# 1-Schematic_210_Project_Wearable.net
KiCad netlist of a schematic drawn in EasyEDA
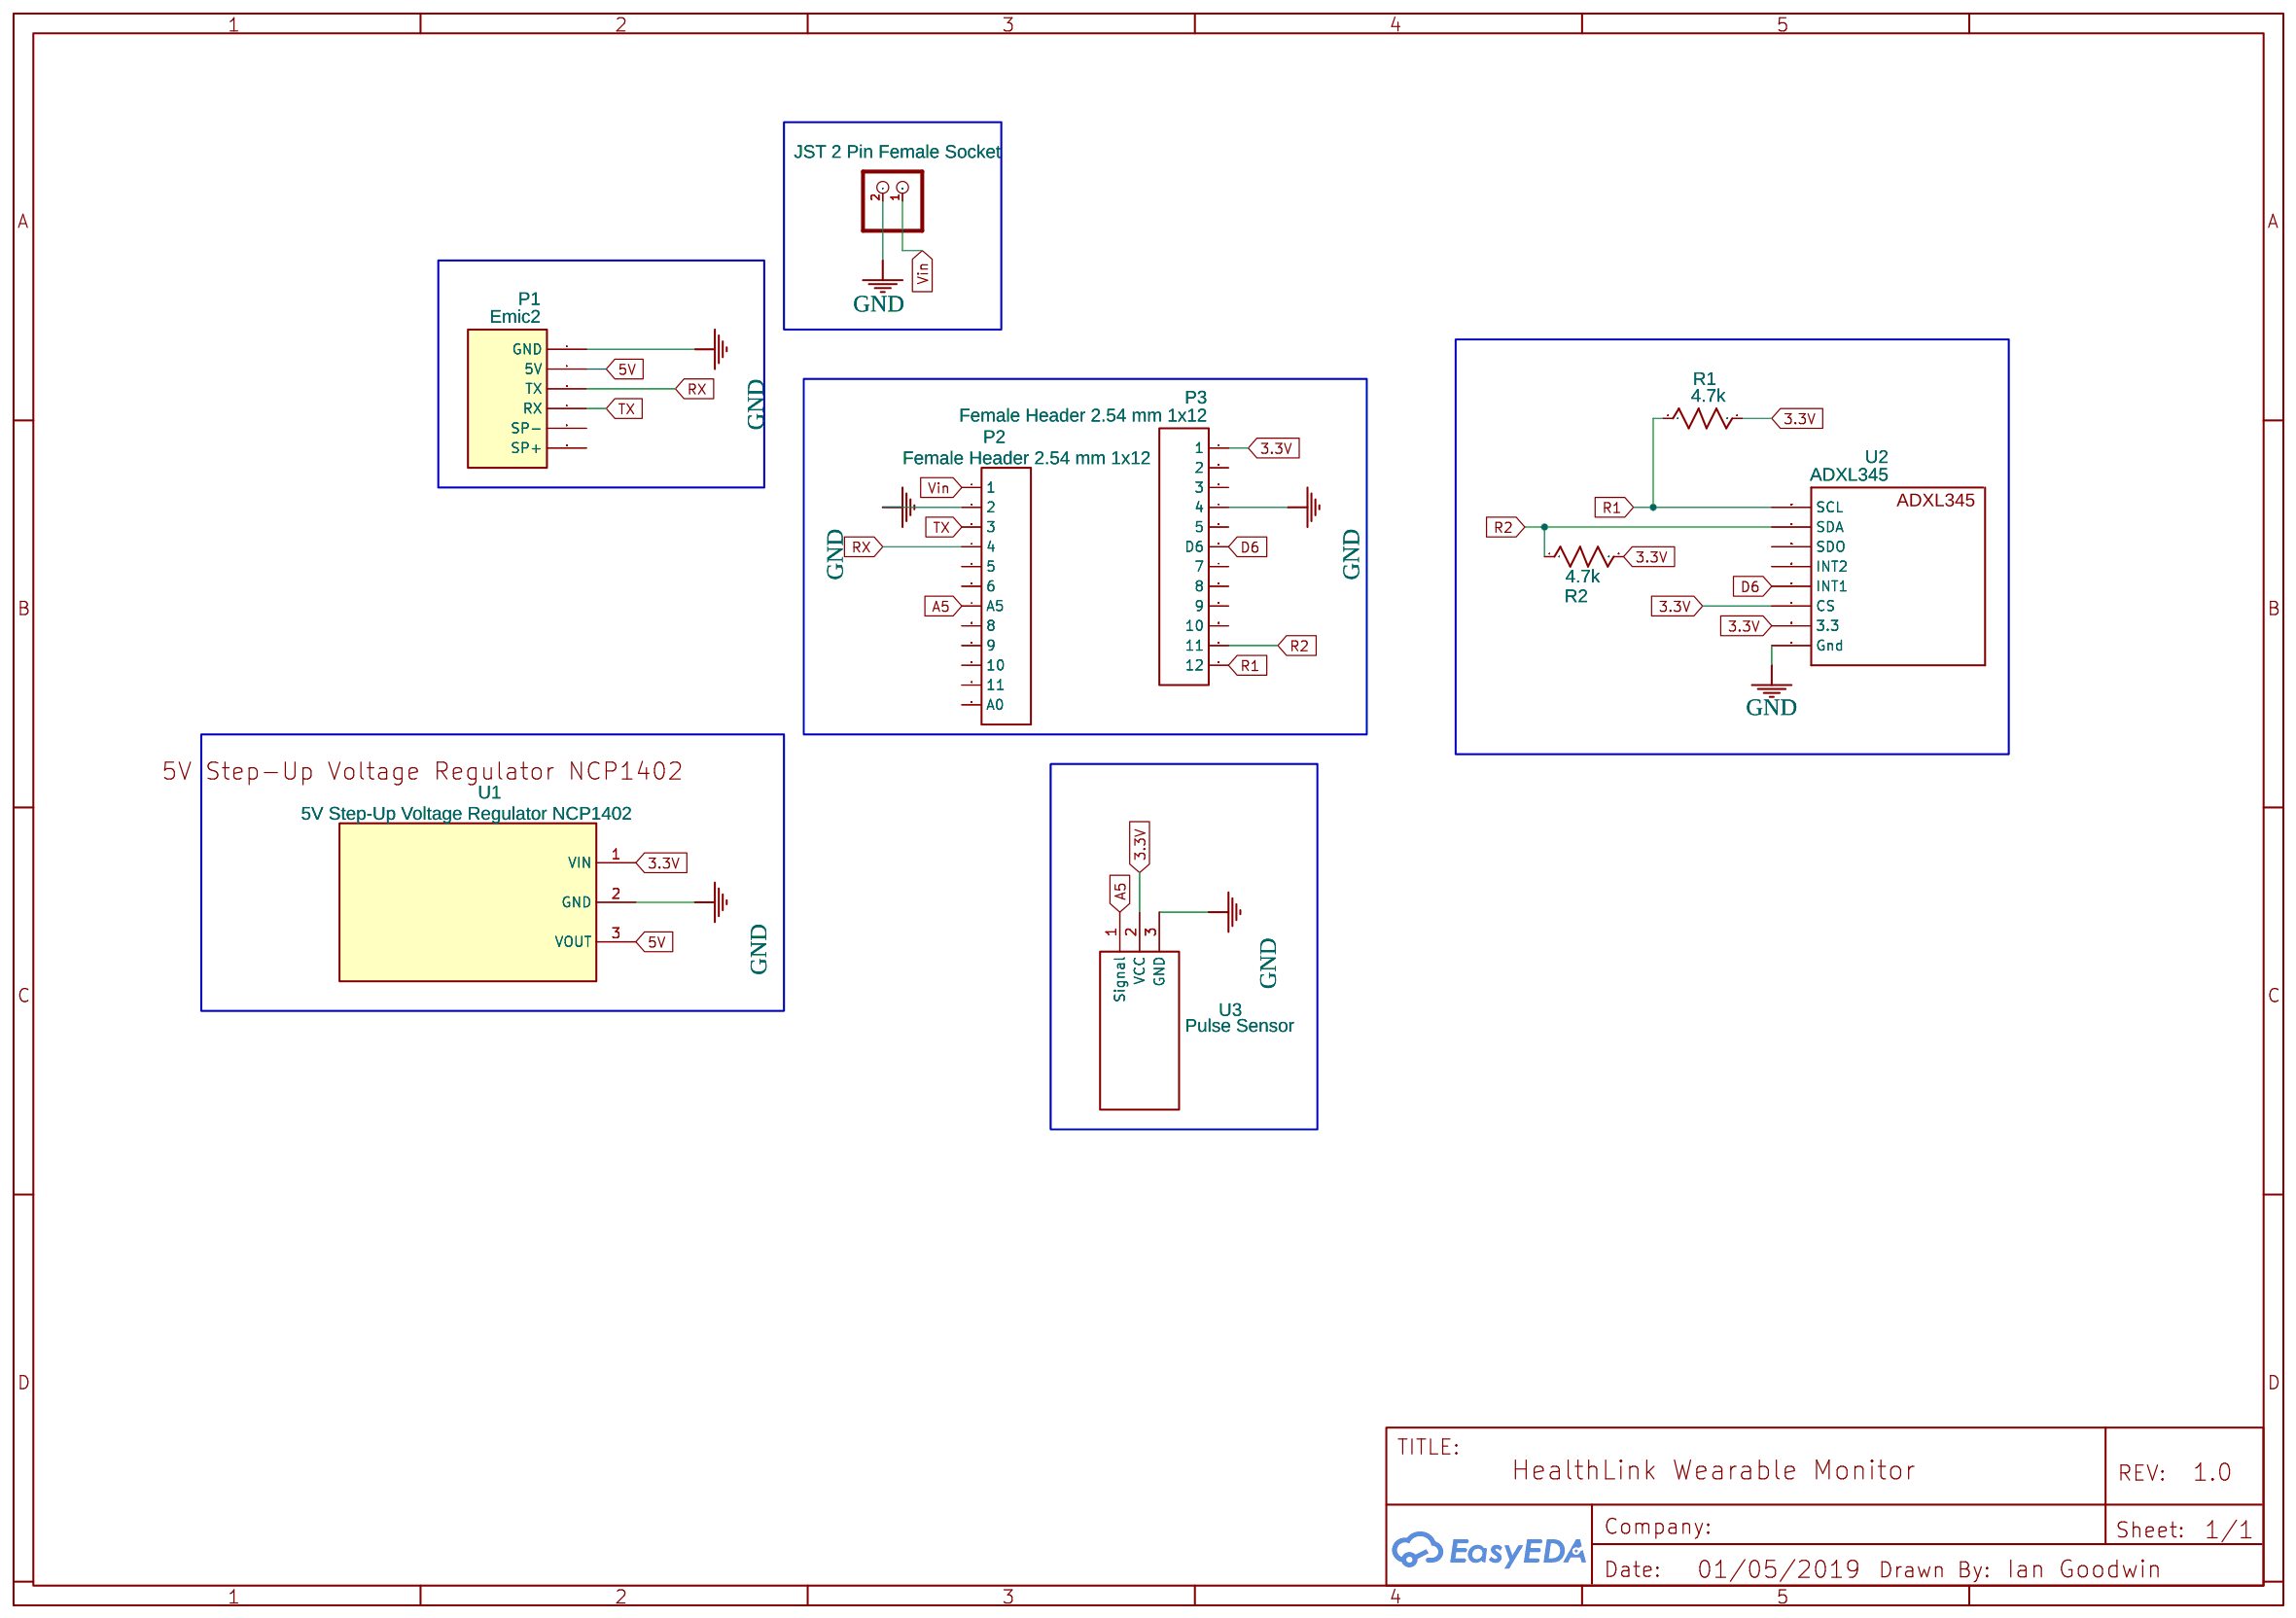
[diagram p0: schematic sheet]

(export (version "E")
  (design (tool "Eeschema 10.0.6"))
  (components
    (comp (ref "CN1")
      (value "JST 2 Pin Female Socket")
      (fields (field (name "BOM_Manufacturer Part") "?"))
      (libsource (lib "") (part "Unknown_445_95"))
    )
    (comp (ref "P1")
      (value "Emic2")
      (fields (field (name "BOM_Supplier Part") "C50984"))
      (libsource (lib "") (part "Unknown_270_185"))
    )
    (comp (ref "P2")
      (value "Female Header 2.54 mm 1x12")
      (fields (field (name "BOM_Manufacturer Part") "?"))
      (libsource (lib "") (part "Unknown_500_300"))
    )
    (comp (ref "P3")
      (value "Female Header 2.54 mm 1x12")
      (fields (field (name "BOM_Manufacturer Part") "?"))
      (libsource (lib "") (part "Unknown_595_280"))
    )
    (comp (ref "R1")
      (value "4.7k")
      (fields (field (name "BOM_Manufacturer Part") "?"))
      (libsource (lib "") (part "Res_AXIAL-0.3(1/8W)_US"))
    )
    (comp (ref "R2")
      (value "4.7k")
      (fields (field (name "BOM_Manufacturer Part") "?"))
      (libsource (lib "") (part "Res_AXIAL-0.3(1/8W)_US"))
    )
    (comp (ref "U1")
      (value "5V Step-Up Voltage Regulator NCP1402")
      (fields (field (name "BOM_Manufacturer Part") "?"))
      (libsource (lib "") (part "Unknown_225_440"))
    )
    (comp (ref "U2")
      (value "ADXL345")
      (fields (field (name "BOM_Manufacturer Part") "?"))
      (libsource (lib "") (part "Unknown_965_280"))
    )
    (comp (ref "U3")
      (value "Pulse Sensor")
      (fields (field (name "BOM_Manufacturer Part") "New SchematicLib"))
      (libsource (lib "") (part "Unknown_570_495"))
    )
  )
  (nets
    (net (code "1") (name "3.3V") (class "Default")
      (node (ref "P3") (pin "1") (pinfunction "1_1") (pintype "input"))
      (node (ref "R1") (pin "2") (pinfunction "2_2") (pintype "unspecified"))
      (node (ref "R2") (pin "2") (pinfunction "2_2") (pintype "unspecified"))
      (node (ref "U1") (pin "1") (pinfunction "VIN_1") (pintype "unspecified"))
      (node (ref "U2") (pin "P$5") (pinfunction "3.3_P$5") (pintype "unspecified"))
      (node (ref "U2") (pin "P$7") (pinfunction "CS_P$7") (pintype "unspecified"))
      (node (ref "U3") (pin "2") (pinfunction "VCC_2") (pintype "unspecified"))
    )
    (net (code "2") (name "5V") (class "Default")
      (node (ref "P1") (pin "2") (pinfunction "5V_2") (pintype "input"))
      (node (ref "U1") (pin "3") (pinfunction "VOUT_3") (pintype "unspecified"))
    )
    (net (code "3") (name "A5") (class "Default")
      (node (ref "P2") (pin "7") (pinfunction "A5_7") (pintype "input"))
      (node (ref "U3") (pin "1") (pinfunction "Signal_1") (pintype "unspecified"))
    )
    (net (code "4") (name "D6") (class "Default")
      (node (ref "P3") (pin "6") (pinfunction "D6_6") (pintype "input"))
      (node (ref "U2") (pin "P$8") (pinfunction "INT1_P$8") (pintype "unspecified"))
    )
    (net (code "5") (name "GND") (class "Default")
      (node (ref "CN1") (pin "2") (pinfunction "1_2") (pintype "unspecified"))
      (node (ref "P1") (pin "1") (pinfunction "GND_1") (pintype "input"))
      (node (ref "P2") (pin "2") (pinfunction "2_2") (pintype "input"))
      (node (ref "P3") (pin "4") (pinfunction "4_4") (pintype "input"))
      (node (ref "U1") (pin "2") (pinfunction "GND_2") (pintype "unspecified"))
      (node (ref "U2") (pin "P$6") (pinfunction "Gnd_P$6") (pintype "unspecified"))
      (node (ref "U3") (pin "3") (pinfunction "GND_3") (pintype "unspecified"))
    )
    (net (code "6") (name "R1") (class "Default")
      (node (ref "P3") (pin "12") (pinfunction "12_12") (pintype "input"))
      (node (ref "R1") (pin "1") (pinfunction "1_1") (pintype "unspecified"))
      (node (ref "U2") (pin "P$12") (pinfunction "SCL_P$12") (pintype "unspecified"))
    )
    (net (code "7") (name "R2") (class "Default")
      (node (ref "P3") (pin "11") (pinfunction "11_11") (pintype "input"))
      (node (ref "R2") (pin "1") (pinfunction "1_1") (pintype "unspecified"))
      (node (ref "U2") (pin "P$11") (pinfunction "SDA_P$11") (pintype "unspecified"))
    )
    (net (code "8") (name "RX") (class "Default")
      (node (ref "P1") (pin "3") (pinfunction "TX_3") (pintype "input"))
      (node (ref "P2") (pin "4") (pinfunction "4_4") (pintype "input"))
    )
    (net (code "9") (name "TX") (class "Default")
      (node (ref "P1") (pin "4") (pinfunction "RX_4") (pintype "input"))
      (node (ref "P2") (pin "3") (pinfunction "3_3") (pintype "input"))
    )
    (net (code "10") (name "Vin") (class "Default")
      (node (ref "CN1") (pin "1") (pinfunction "2_1") (pintype "unspecified"))
      (node (ref "P2") (pin "1") (pinfunction "1_1") (pintype "input"))
    )
    (net (code "11") (name "unconnected-(P1-SP+-Pad6)") (class "Default")
      (node (ref "P1") (pin "6") (pinfunction "SP+_6") (pintype "input"))
    )
    (net (code "12") (name "unconnected-(P1-SP--Pad5)") (class "Default")
      (node (ref "P1") (pin "5") (pinfunction "SP-_5") (pintype "input"))
    )
    (net (code "13") (name "unconnected-(P2-A0-Pad12)") (class "Default")
      (node (ref "P2") (pin "12") (pinfunction "A0_12") (pintype "input"))
    )
    (net (code "14") (name "unconnected-(P2-Pad5)") (class "Default")
      (node (ref "P2") (pin "5") (pinfunction "5_5") (pintype "input"))
    )
    (net (code "15") (name "unconnected-(P2-Pad6)") (class "Default")
      (node (ref "P2") (pin "6") (pinfunction "6_6") (pintype "input"))
    )
    (net (code "16") (name "unconnected-(P2-Pad8)") (class "Default")
      (node (ref "P2") (pin "8") (pinfunction "8_8") (pintype "input"))
    )
    (net (code "17") (name "unconnected-(P2-Pad9)") (class "Default")
      (node (ref "P2") (pin "9") (pinfunction "9_9") (pintype "input"))
    )
    (net (code "18") (name "unconnected-(P2-Pad10)") (class "Default")
      (node (ref "P2") (pin "10") (pinfunction "10_10") (pintype "input"))
    )
    (net (code "19") (name "unconnected-(P2-Pad11)") (class "Default")
      (node (ref "P2") (pin "11") (pinfunction "11_11") (pintype "input"))
    )
    (net (code "20") (name "unconnected-(P3-Pad2)") (class "Default")
      (node (ref "P3") (pin "2") (pinfunction "2_2") (pintype "input"))
    )
    (net (code "21") (name "unconnected-(P3-Pad3)") (class "Default")
      (node (ref "P3") (pin "3") (pinfunction "3_3") (pintype "input"))
    )
    (net (code "22") (name "unconnected-(P3-Pad5)") (class "Default")
      (node (ref "P3") (pin "5") (pinfunction "5_5") (pintype "input"))
    )
    (net (code "23") (name "unconnected-(P3-Pad7)") (class "Default")
      (node (ref "P3") (pin "7") (pinfunction "7_7") (pintype "input"))
    )
    (net (code "24") (name "unconnected-(P3-Pad8)") (class "Default")
      (node (ref "P3") (pin "8") (pinfunction "8_8") (pintype "input"))
    )
    (net (code "25") (name "unconnected-(P3-Pad9)") (class "Default")
      (node (ref "P3") (pin "9") (pinfunction "9_9") (pintype "input"))
    )
    (net (code "26") (name "unconnected-(P3-Pad10)") (class "Default")
      (node (ref "P3") (pin "10") (pinfunction "10_10") (pintype "input"))
    )
    (net (code "27") (name "unconnected-(U2-INT2-PadP$9)") (class "Default")
      (node (ref "U2") (pin "P$9") (pinfunction "INT2_P$9") (pintype "unspecified"))
    )
    (net (code "28") (name "unconnected-(U2-SDO-PadP$10)") (class "Default")
      (node (ref "U2") (pin "P$10") (pinfunction "SDO_P$10") (pintype "unspecified"))
    )
  )
)
